# main.net
KiCad netlist of a schematic drawn in EAGLE
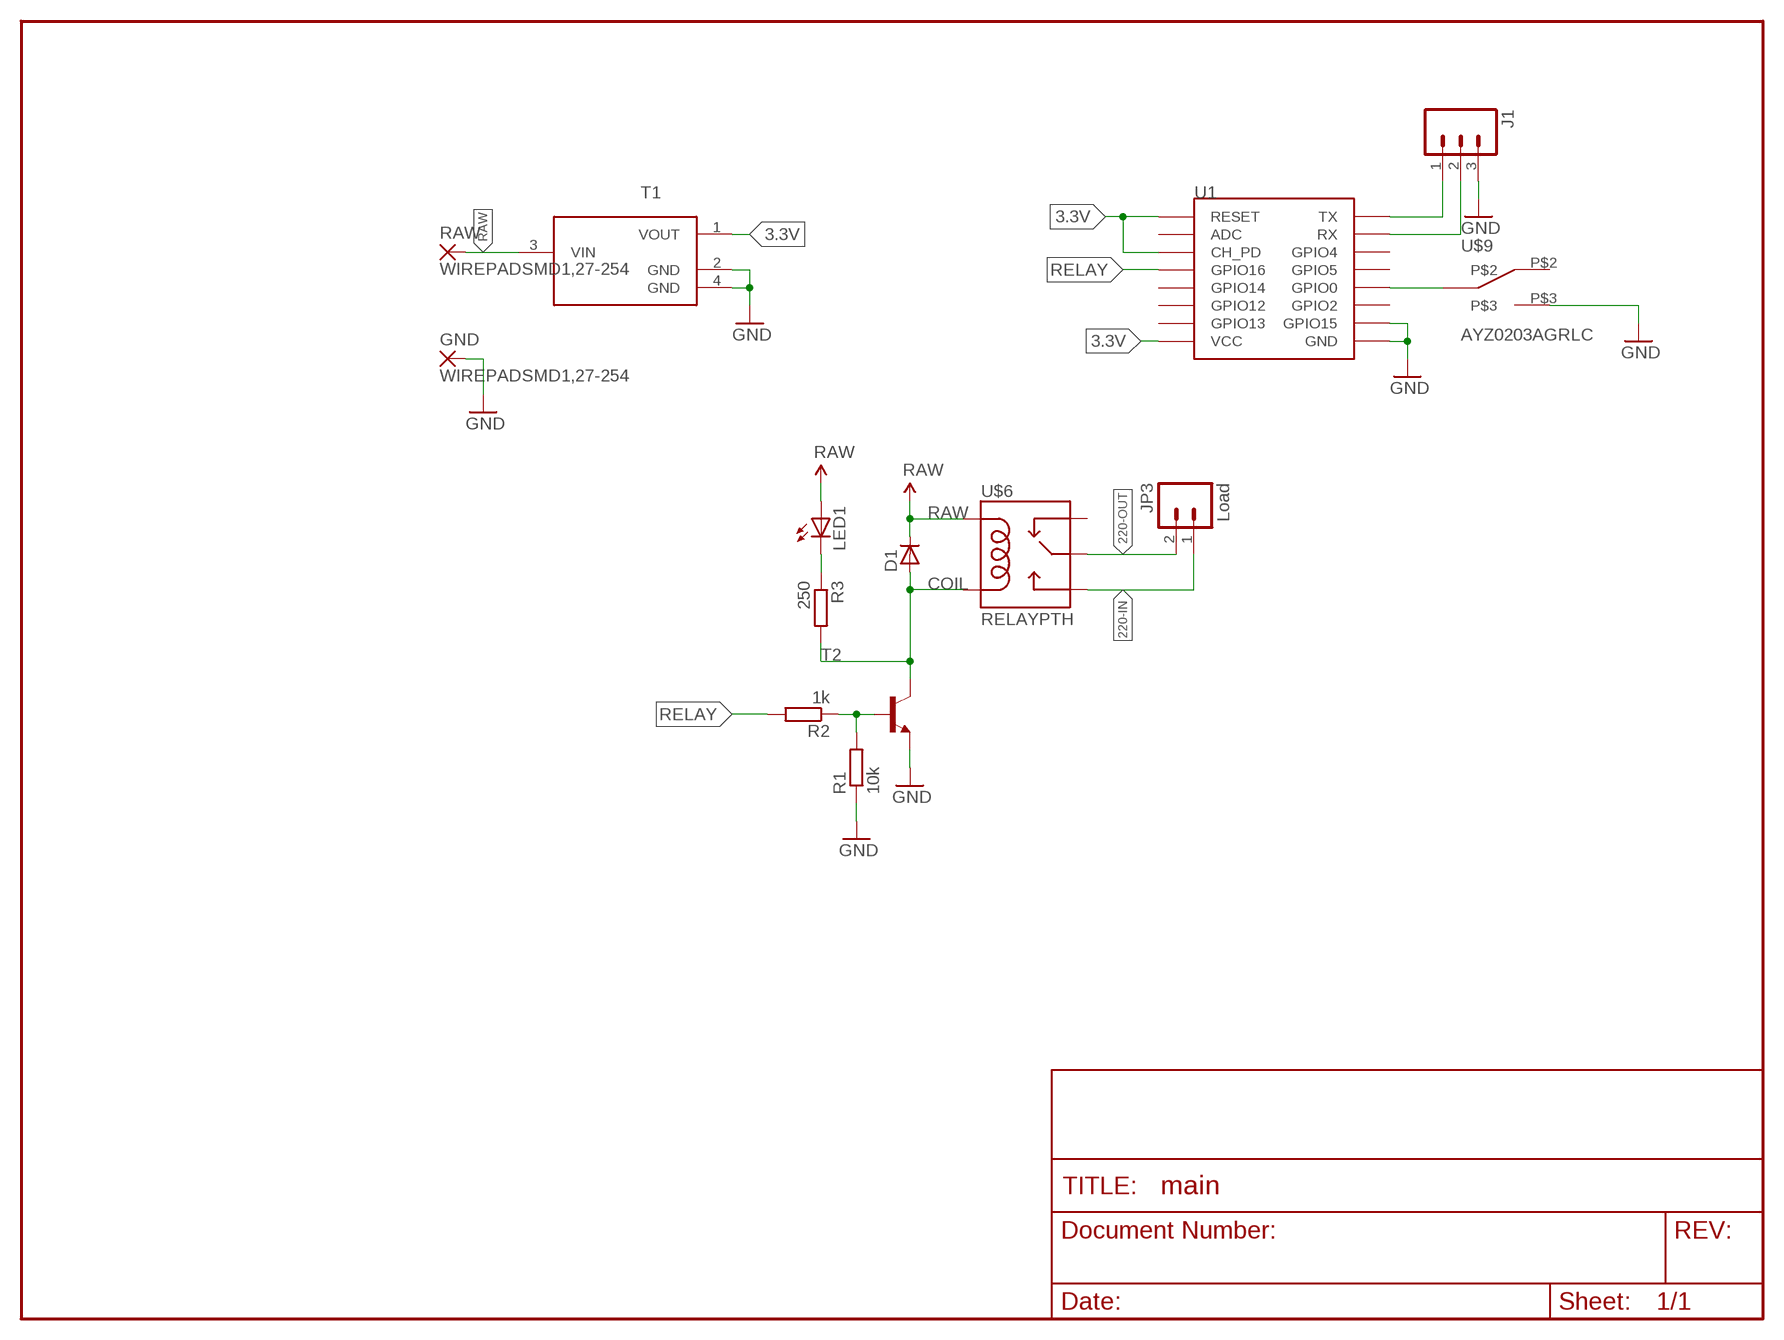
[diagram p0: schematic, sheet 1]

(export (version "E")
  (design (tool "Eeschema 10.0.6"))
  (components
    (comp (ref "D1")
      (value "D-A1-C3")
      (footprint "eagle-import:SOT23")
      (libsource (lib "eagle-import") (part "D-A1-C3"))
    )
    (comp (ref "GND")
      (value "WIREPADSMD1,27-254")
      (footprint "eagle-import:SMD1,27-2,54")
      (libsource (lib "eagle-import") (part "WIREPADSMD1,27-254"))
    )
    (comp (ref "J1")
      (value "M03PTH")
      (footprint "eagle-import:1X03")
      (libsource (lib "eagle-import") (part "M03PTH"))
    )
    (comp (ref "JP3")
      (value "Load")
      (footprint "eagle-import:SCREWTERMINAL-5MM-2")
      (libsource (lib "eagle-import") (part "M025MM"))
    )
    (comp (ref "LED1")
      (value "LEDCHIPLED_0603")
      (footprint "eagle-import:CHIPLED_0603")
      (libsource (lib "eagle-import") (part "LEDCHIPLED_0603"))
    )
    (comp (ref "R1")
      (value "10k")
      (footprint "eagle-import:R0603")
      (libsource (lib "eagle-import") (part "R-EU_R0603"))
    )
    (comp (ref "R2")
      (value "1k")
      (footprint "eagle-import:R0603")
      (libsource (lib "eagle-import") (part "R-EU_R0603"))
    )
    (comp (ref "R3")
      (value "250")
      (footprint "eagle-import:R0603")
      (libsource (lib "eagle-import") (part "R-EU_R0603"))
    )
    (comp (ref "RAW")
      (value "WIREPADSMD1,27-254")
      (footprint "eagle-import:SMD1,27-2,54")
      (libsource (lib "eagle-import") (part "WIREPADSMD1,27-254"))
    )
    (comp (ref "T1")
      (value "L78L33ACUTR")
      (footprint "eagle-import:SOT150P400X160-4N")
      (libsource (lib "eagle-import") (part "L78L33ACUTR"))
    )
    (comp (ref "T2")
      (value "BC808-NPN-SOT23-BEC")
      (footprint "eagle-import:SOT23-BEC")
      (libsource (lib "eagle-import") (part "-NPN-SOT23-BECBC808"))
    )
    (comp (ref "U$6")
      (value "RELAYPTH")
      (footprint "eagle-import:RELAY-G5Q")
      (libsource (lib "eagle-import") (part "RELAYPTH"))
    )
    (comp (ref "U$9")
      (value "AYZ0203AGRLC")
      (footprint "eagle-import:AYZ0203AGRLC")
      (libsource (lib "eagle-import") (part "AYZ0203AGRLC"))
    )
    (comp (ref "U1")
      (value "ESP12SMD")
      (footprint "eagle-import:ESP12-SMD")
      (libsource (lib "eagle-import") (part "ESP12SMD"))
    )
  )
  (nets
    (net (code "1") (name "/COIL") (class "Default")
      (node (ref "D1") (pin "1") (pinfunction "A_1") (pintype "passive"))
      (node (ref "R3") (pin "2") (pinfunction "2_2") (pintype "passive"))
      (node (ref "T2") (pin "C") (pinfunction "C_C") (pintype "passive"))
      (node (ref "U$6") (pin "1") (pinfunction "COIL2_1") (pintype "bidirectional"))
    )
    (net (code "2") (name "3.3V") (class "Default")
      (node (ref "T1") (pin "1") (pinfunction "VOUT_1") (pintype "output"))
      (node (ref "U1") (pin "CH_PD") (pinfunction "CH_PD_CH_PD") (pintype "bidirectional"))
      (node (ref "U1") (pin "RESET") (pinfunction "RESET_RESET") (pintype "bidirectional"))
      (node (ref "U1") (pin "VCC") (pinfunction "VCC_VCC") (pintype "bidirectional"))
    )
    (net (code "3") (name "220-IN") (class "Default")
      (node (ref "JP3") (pin "1") (pinfunction "1_1") (pintype "passive"))
      (node (ref "U$6") (pin "3") (pinfunction "NO_3") (pintype "bidirectional"))
    )
    (net (code "4") (name "220-OUT") (class "Default")
      (node (ref "JP3") (pin "2") (pinfunction "2_2") (pintype "passive"))
      (node (ref "U$6") (pin "2") (pinfunction "MAIN_2") (pintype "bidirectional"))
    )
    (net (code "5") (name "GND") (class "Default")
      (node (ref "GND") (pin "1") (pinfunction "P_1") (pintype "passive"))
      (node (ref "J1") (pin "3") (pinfunction "3_3") (pintype "passive"))
      (node (ref "R1") (pin "1") (pinfunction "1_1") (pintype "passive"))
      (node (ref "T1") (pin "2") (pinfunction "GND_2") (pintype "power_in"))
      (node (ref "T1") (pin "4") (pinfunction "GND_4") (pintype "power_in"))
      (node (ref "T2") (pin "E") (pinfunction "E_E") (pintype "passive"))
      (node (ref "U$9") (pin "P$3") (pinfunction "P$3_P$3") (pintype "bidirectional"))
      (node (ref "U1") (pin "GND") (pinfunction "GND_GND") (pintype "bidirectional"))
      (node (ref "U1") (pin "GPIO15") (pinfunction "GPIO15_GPIO15") (pintype "bidirectional"))
    )
    (net (code "6") (name "Net-(LED1-PadC)") (class "Default")
      (node (ref "LED1") (pin "C") (pinfunction "C_C") (pintype "passive"))
      (node (ref "R3") (pin "1") (pinfunction "1_1") (pintype "passive"))
    )
    (net (code "7") (name "Net-(R1-Pad2)") (class "Default")
      (node (ref "R1") (pin "2") (pinfunction "2_2") (pintype "passive"))
      (node (ref "R2") (pin "1") (pinfunction "1_1") (pintype "passive"))
      (node (ref "T2") (pin "B") (pinfunction "B_B") (pintype "passive"))
    )
    (net (code "8") (name "Net-(U$9-COM)") (class "Default")
      (node (ref "U$9") (pin "P$1") (pinfunction "COM_P$1") (pintype "bidirectional"))
      (node (ref "U1") (pin "GPIO0") (pinfunction "GPIO0_GPIO0") (pintype "bidirectional"))
    )
    (net (code "9") (name "Net-(U1-RX)") (class "Default")
      (node (ref "J1") (pin "2") (pinfunction "2_2") (pintype "passive"))
      (node (ref "U1") (pin "RXD0") (pinfunction "RX_RXD0") (pintype "bidirectional"))
    )
    (net (code "10") (name "Net-(U1-TX)") (class "Default")
      (node (ref "J1") (pin "1") (pinfunction "1_1") (pintype "passive"))
      (node (ref "U1") (pin "TXD0") (pinfunction "TX_TXD0") (pintype "bidirectional"))
    )
    (net (code "11") (name "RAW") (class "Default")
      (node (ref "D1") (pin "3") (pinfunction "C_3") (pintype "passive"))
      (node (ref "LED1") (pin "A") (pinfunction "A_A") (pintype "passive"))
      (node (ref "RAW") (pin "1") (pinfunction "P_1") (pintype "passive"))
      (node (ref "T1") (pin "3") (pinfunction "VIN_3") (pintype "input"))
      (node (ref "U$6") (pin "5") (pinfunction "COIL1_5") (pintype "bidirectional"))
    )
    (net (code "12") (name "RELAY") (class "Default")
      (node (ref "R2") (pin "2") (pinfunction "2_2") (pintype "passive"))
      (node (ref "U1") (pin "GPIO16") (pinfunction "GPIO16_GPIO16") (pintype "bidirectional"))
    )
    (net (code "13") (name "unconnected-(U$6-NC-Pad4)") (class "Default")
      (node (ref "U$6") (pin "4") (pinfunction "NC_4") (pintype "bidirectional"))
    )
    (net (code "14") (name "unconnected-(U$9-PadP$2)") (class "Default")
      (node (ref "U$9") (pin "P$2") (pinfunction "P$2_P$2") (pintype "bidirectional"))
    )
    (net (code "15") (name "unconnected-(U1-PadADC)") (class "Default")
      (node (ref "U1") (pin "ADC") (pinfunction "ADC_ADC") (pintype "bidirectional"))
    )
    (net (code "16") (name "unconnected-(U1-PadGPIO2)") (class "Default")
      (node (ref "U1") (pin "GPIO2") (pinfunction "GPIO2_GPIO2") (pintype "bidirectional"))
    )
    (net (code "17") (name "unconnected-(U1-PadGPIO4)") (class "Default")
      (node (ref "U1") (pin "GPIO4") (pinfunction "GPIO4_GPIO4") (pintype "bidirectional"))
    )
    (net (code "18") (name "unconnected-(U1-PadGPIO5)") (class "Default")
      (node (ref "U1") (pin "GPIO5") (pinfunction "GPIO5_GPIO5") (pintype "bidirectional"))
    )
    (net (code "19") (name "unconnected-(U1-PadGPIO12)") (class "Default")
      (node (ref "U1") (pin "GPIO12") (pinfunction "GPIO12_GPIO12") (pintype "bidirectional"))
    )
    (net (code "20") (name "unconnected-(U1-PadGPIO13)") (class "Default")
      (node (ref "U1") (pin "GPIO13") (pinfunction "GPIO13_GPIO13") (pintype "bidirectional"))
    )
    (net (code "21") (name "unconnected-(U1-PadGPIO14)") (class "Default")
      (node (ref "U1") (pin "GPIO14") (pinfunction "GPIO14_GPIO14") (pintype "bidirectional"))
    )
  )
)
